# VF_sch.net
KiCad netlist of a schematic drawn in Altium Designer
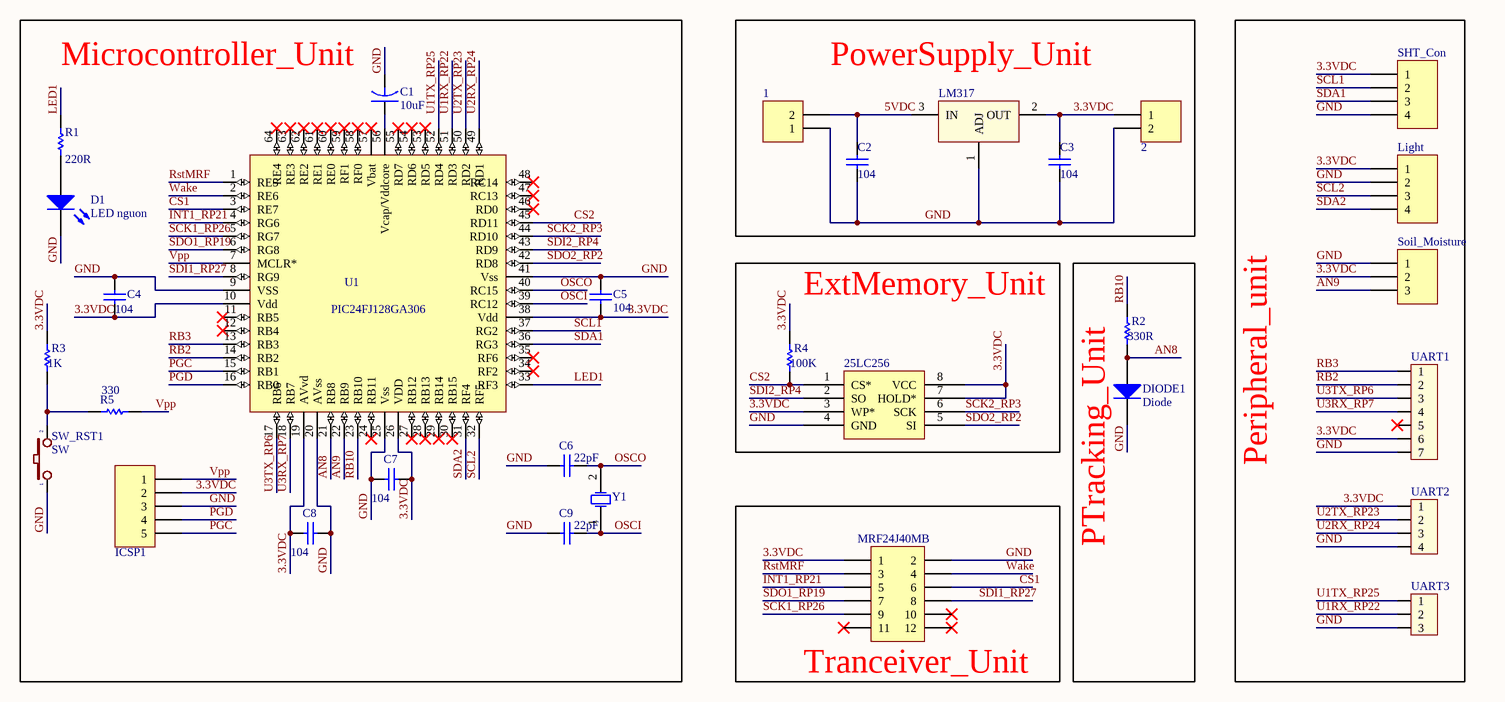
[diagram p0: VF_sch.SchDoc]

(export (version "E")
  (design (tool "Eeschema 10.0.6"))
  (components
    (comp (ref "1")
      (value "Header 2")
      (footprint "HDR1X2")
      (description "Header, 2-Pin")
      (fields (field (name "PUBLISHER") "Altium Limited"))
      (libsource (lib "") (part "Header 2_1"))
    )
    (comp (ref "2")
      (value "3.3V DC")
      (footprint "HDR1X2")
      (description "Header, 2-Pin")
      (fields (field (name "PUBLISHER") "Altium Limited"))
      (libsource (lib "Miscellaneous Connectors") (part "Header 2"))
    )
    (comp (ref "3") (value "25LC256") (footprint "DIP-8") (libsource (lib "25LC256") (part "25LC256")))
    (comp (ref "C1")
      (value "10uF")
      (footprint "MH_DA_THU_VIEN_16122016:CP1/2.5_SM")
      (libsource (lib "ThinhNguyenLib") (part "CAPACITOR"))
    )
    (comp (ref "C2")
      (value "104")
      (footprint "C0805")
      (description "Capacitor")
      (fields (field (name "Comment") "Cap") (field (name "PUBLISHER") "Altium Limited"))
      (libsource (lib "Miscellaneous Devices") (part "Cap"))
    )
    (comp (ref "C3")
      (value "104")
      (footprint "C0805")
      (description "Capacitor")
      (fields (field (name "Comment") "Cap") (field (name "PUBLISHER") "Altium Limited"))
      (libsource (lib "Miscellaneous Devices") (part "Cap"))
    )
    (comp (ref "C4")
      (value "104")
      (footprint "C0805")
      (description "Capacitor")
      (fields (field (name "Comment") "Cap") (field (name "PUBLISHER") "Altium Limited"))
      (libsource (lib "Miscellaneous Devices") (part "Cap"))
    )
    (comp (ref "C5")
      (value "104")
      (footprint "RAD-0.3")
      (description "Capacitor")
      (fields (field (name "PUBLISHER") "Altium Limited"))
      (libsource (lib "Miscellaneous Devices") (part "Cap"))
    )
    (comp (ref "C6")
      (value "22pF")
      (footprint "C0805")
      (description "Capacitor")
      (fields (field (name "Comment") "Cap") (field (name "PUBLISHER") "Altium Limited"))
      (libsource (lib "Miscellaneous Devices") (part "Cap"))
    )
    (comp (ref "C7")
      (value "104")
      (footprint "C0805")
      (description "Capacitor")
      (fields (field (name "Comment") "Cap") (field (name "PUBLISHER") "Altium Limited"))
      (libsource (lib "Miscellaneous Devices") (part "Cap"))
    )
    (comp (ref "C8")
      (value "104")
      (footprint "C0805")
      (description "Capacitor")
      (fields (field (name "Comment") "Cap") (field (name "PUBLISHER") "Altium Limited"))
      (libsource (lib "Miscellaneous Devices") (part "Cap"))
    )
    (comp (ref "C9")
      (value "22pF")
      (footprint "C0805")
      (description "Capacitor")
      (fields (field (name "Comment") "Cap") (field (name "PUBLISHER") "Altium Limited"))
      (libsource (lib "Miscellaneous Devices") (part "Cap"))
    )
    (comp (ref "D1")
      (value "LED nguon")
      (footprint "LED3mm")
      (description "Typical INFRARED GaAs LED")
      (fields (field (name "PUBLISHER") "Altium Limited"))
      (libsource (lib "Miscellaneous Devices") (part "LED0"))
    )
    (comp (ref "DIODE1")
      (value "Diode")
      (footprint "DZ0.5A")
      (description "Default Diode")
      (fields (field (name "PUBLISHER") "Altium Limited"))
      (libsource (lib "Miscellaneous Devices") (part "Diode"))
    )
    (comp (ref "ICSP1")
      (value "ICSP")
      (footprint "CON5")
      (description "Header, 5-Pin")
      (fields (field (name "PUBLISHER") "Altium Limited"))
      (libsource (lib "Miscellaneous Connectors") (part "Header 5"))
    )
    (comp (ref "LM317")
      (value "LM317")
      (footprint "SOT223-4N")
      (description "Adj Voltage +1.2 -> +37V")
      (libsource (lib "syhaunguyen") (part "LM317"))
    )
    (comp (ref "MRF1")
      (value "MRF24J40MB")
      (footprint "HDR2X6")
      (description "Header, 6-Pin, Dual row")
      (fields (field (name "PUBLISHER") "Altium Limited"))
      (libsource (lib "Miscellaneous Connectors") (part "Header 6X2"))
    )
    (comp (ref "P1")
      (value "Light")
      (footprint "HDR1X4")
      (description "Header, 4-Pin")
      (fields (field (name "PUBLISHER") "Altium Limited"))
      (libsource (lib "Miscellaneous Connectors") (part "Header 4"))
    )
    (comp (ref "R1")
      (value "220R")
      (footprint "C0805")
      (description "Resistor")
      (fields (field (name "Comment") "Res1") (field (name "PUBLISHER") "Altium Limited"))
      (libsource (lib "Miscellaneous Devices") (part "Res1"))
    )
    (comp (ref "R2")
      (value "330R")
      (footprint "C0805")
      (description "Resistor")
      (fields (field (name "Comment") "Res1") (field (name "PUBLISHER") "Altium Limited"))
      (libsource (lib "Miscellaneous Devices") (part "Res1"))
    )
    (comp (ref "R3")
      (value "1K")
      (footprint "C0805")
      (description "Resistor")
      (fields (field (name "Comment") "Res1") (field (name "PUBLISHER") "Altium Limited"))
      (libsource (lib "Miscellaneous Devices") (part "Res1"))
    )
    (comp (ref "R4")
      (value "100K")
      (footprint "C0805")
      (description "Semiconductor Resistor")
      (fields (field (name "Comment") "Res Semi") (field (name "PUBLISHER") "Altium Limited"))
      (libsource (lib "Miscellaneous Devices") (part "Res Semi"))
    )
    (comp (ref "R5")
      (value "330")
      (footprint "C0805")
      (description "Resistor")
      (fields (field (name "Comment") "res") (field (name "PUBLISHER") "Altium Limited"))
      (libsource (lib "Miscellaneous Devices") (part "Res1"))
    )
    (comp (ref "SHT_CON1")
      (value "SHT_Con")
      (footprint "CON4")
      (description "Header, 4-Pin")
      (fields (field (name "PUBLISHER") "Altium Limited"))
      (libsource (lib "Miscellaneous Connectors") (part "Header 4"))
    )
    (comp (ref "Soil_Moisture")
      (value "Header 3")
      (footprint "HDR1X3")
      (description "Header, 3-Pin")
      (fields (field (name "PUBLISHER") "Altium Limited"))
      (libsource (lib "Miscellaneous Connectors") (part "Header 3"))
    )
    (comp (ref "SW_RST1")
      (value "SW")
      (footprint "SW2")
      (description "Switch button 2 pin")
      (libsource (lib "syhaunguyen") (part "SW2"))
    )
    (comp (ref "U1")
      (value "PIC24FJ128GA306")
      (footprint "MCHP-TQFP-PT64_M")
      (libsource (lib "Mylibbrary") (part "PIC24FJ128GA306"))
    )
    (comp (ref "UART1")
      (value "LORA_TRANCEIVER")
      (footprint "CON7")
      (description "Connector 7")
      (libsource (lib "syhaunguyen") (part "Con7"))
    )
    (comp (ref "UART2")
      (value "UART2")
      (footprint "CON4")
      (description "Connector 4")
      (libsource (lib "syhaunguyen") (part "Con4"))
    )
    (comp (ref "UART3")
      (value "~")
      (footprint "CON3")
      (description "Connector 3")
      (libsource (lib "syhaunguyen") (part "Con3"))
    )
    (comp (ref "Y1")
      (value "XTAL")
      (footprint "XT2")
      (description "Crystal Oscillator")
      (fields (field (name "PUBLISHER") "Altium Limited"))
      (libsource (lib "Miscellaneous Devices") (part "XTAL"))
    )
  )
  (nets
    (net (code "1") (name "/3.3VDC") (class "Default")
      (node (ref "2") (pin "1") (pinfunction "1_1") (pintype "passive"))
      (node (ref "3") (pin "3") (pinfunction "WP*_3") (pintype "passive"))
      (node (ref "3") (pin "7") (pinfunction "HOLD*_7") (pintype "passive"))
      (node (ref "3") (pin "8") (pinfunction "VCC_8") (pintype "power_in"))
      (node (ref "C3") (pin "2") (pinfunction "2_2") (pintype "passive"))
      (node (ref "C4") (pin "1") (pinfunction "1_1") (pintype "passive"))
      (node (ref "C5") (pin "1") (pinfunction "1_1") (pintype "passive"))
      (node (ref "C7") (pin "2") (pinfunction "2_2") (pintype "passive"))
      (node (ref "C8") (pin "1") (pinfunction "1_1") (pintype "passive"))
      (node (ref "ICSP1") (pin "2") (pinfunction "2_2") (pintype "passive"))
      (node (ref "LM317") (pin "2") (pinfunction "OUT_2") (pintype "passive"))
      (node (ref "MRF1") (pin "1") (pinfunction "1_1") (pintype "passive"))
      (node (ref "P1") (pin "1") (pinfunction "1_1") (pintype "passive"))
      (node (ref "R3") (pin "2") (pinfunction "2_2") (pintype "passive"))
      (node (ref "R4") (pin "2") (pinfunction "2_2") (pintype "passive"))
      (node (ref "SHT_CON1") (pin "1") (pinfunction "1_1") (pintype "passive"))
      (node (ref "Soil_Moisture") (pin "2") (pinfunction "2_2") (pintype "passive"))
      (node (ref "U1") (pin "10") (pinfunction "Vdd_10") (pintype "passive"))
      (node (ref "U1") (pin "19") (pinfunction "AVvd_19") (pintype "power_in"))
      (node (ref "U1") (pin "26") (pinfunction "VDD_26") (pintype "power_in"))
      (node (ref "U1") (pin "38") (pinfunction "Vdd_38") (pintype "power_in"))
      (node (ref "UART1") (pin "6") (pinfunction "6_6") (pintype "passive"))
      (node (ref "UART2") (pin "1") (pinfunction "1_1") (pintype "passive"))
    )
    (net (code "2") (name "/5VDC") (class "Default")
      (node (ref "1") (pin "2") (pinfunction "2_2") (pintype "passive"))
      (node (ref "C2") (pin "2") (pinfunction "2_2") (pintype "passive"))
      (node (ref "LM317") (pin "3") (pinfunction "IN_3") (pintype "passive"))
    )
    (net (code "3") (name "/AN8") (class "Default")
      (node (ref "DIODE1") (pin "1") (pinfunction "A_1") (pintype "passive"))
      (node (ref "R2") (pin "1") (pinfunction "1_1") (pintype "passive"))
      (node (ref "U1") (pin "21") (pinfunction "RB8_21") (pintype "bidirectional"))
    )
    (net (code "4") (name "/AN9") (class "Default")
      (node (ref "Soil_Moisture") (pin "3") (pinfunction "3_3") (pintype "passive"))
      (node (ref "U1") (pin "22") (pinfunction "RB9_22") (pintype "bidirectional"))
    )
    (net (code "5") (name "/CS1") (class "Default")
      (node (ref "MRF1") (pin "6") (pinfunction "6_6") (pintype "passive"))
      (node (ref "U1") (pin "3") (pinfunction "RE7_3") (pintype "bidirectional"))
    )
    (net (code "6") (name "/CS2") (class "Default")
      (node (ref "3") (pin "1") (pinfunction "CS*_1") (pintype "passive"))
      (node (ref "R4") (pin "1") (pinfunction "1_1") (pintype "passive"))
      (node (ref "U1") (pin "45") (pinfunction "RD11_45") (pintype "bidirectional"))
    )
    (net (code "7") (name "/GND") (class "Default")
      (node (ref "1") (pin "1") (pinfunction "1_1") (pintype "passive"))
      (node (ref "2") (pin "2") (pinfunction "2_2") (pintype "passive"))
      (node (ref "3") (pin "4") (pinfunction "GND_4") (pintype "power_in"))
      (node (ref "C1") (pin "2") (pinfunction "2_2") (pintype "passive"))
      (node (ref "C2") (pin "1") (pinfunction "1_1") (pintype "passive"))
      (node (ref "C3") (pin "1") (pinfunction "1_1") (pintype "passive"))
      (node (ref "C4") (pin "2") (pinfunction "2_2") (pintype "passive"))
      (node (ref "C5") (pin "2") (pinfunction "2_2") (pintype "passive"))
      (node (ref "C6") (pin "1") (pinfunction "1_1") (pintype "passive"))
      (node (ref "C7") (pin "1") (pinfunction "1_1") (pintype "passive"))
      (node (ref "C8") (pin "2") (pinfunction "2_2") (pintype "passive"))
      (node (ref "C9") (pin "1") (pinfunction "1_1") (pintype "passive"))
      (node (ref "D1") (pin "2") (pinfunction "K_2") (pintype "passive"))
      (node (ref "DIODE1") (pin "2") (pinfunction "K_2") (pintype "passive"))
      (node (ref "ICSP1") (pin "3") (pinfunction "3_3") (pintype "passive"))
      (node (ref "LM317") (pin "1") (pinfunction "ADJ_1") (pintype "passive"))
      (node (ref "MRF1") (pin "2") (pinfunction "2_2") (pintype "passive"))
      (node (ref "P1") (pin "2") (pinfunction "2_2") (pintype "passive"))
      (node (ref "SHT_CON1") (pin "4") (pinfunction "4_4") (pintype "passive"))
      (node (ref "SW_RST1") (pin "1") (pinfunction "1_1") (pintype "passive"))
      (node (ref "Soil_Moisture") (pin "1") (pinfunction "1_1") (pintype "passive"))
      (node (ref "U1") (pin "20") (pinfunction "AVss_20") (pintype "power_in"))
      (node (ref "U1") (pin "25") (pinfunction "Vss_25") (pintype "power_in"))
      (node (ref "U1") (pin "41") (pinfunction "Vss_41") (pintype "power_in"))
      (node (ref "U1") (pin "9") (pinfunction "VSS_9") (pintype "power_in"))
      (node (ref "UART1") (pin "7") (pinfunction "7_7") (pintype "passive"))
      (node (ref "UART2") (pin "4") (pinfunction "4_4") (pintype "passive"))
      (node (ref "UART3") (pin "3") (pinfunction "3_3") (pintype "passive"))
    )
    (net (code "8") (name "/INT1_RP21") (class "Default")
      (node (ref "MRF1") (pin "5") (pinfunction "5_5") (pintype "passive"))
      (node (ref "U1") (pin "4") (pinfunction "RG6_4") (pintype "bidirectional"))
    )
    (net (code "9") (name "/LED1") (class "Default")
      (node (ref "R1") (pin "2") (pinfunction "2_2") (pintype "passive"))
      (node (ref "U1") (pin "33") (pinfunction "RF3_33") (pintype "bidirectional"))
    )
    (net (code "10") (name "/OSCI") (class "Default")
      (node (ref "C9") (pin "2") (pinfunction "2_2") (pintype "passive"))
      (node (ref "U1") (pin "39") (pinfunction "RC12_39") (pintype "bidirectional"))
      (node (ref "Y1") (pin "1") (pinfunction "OSC1_1") (pintype "passive"))
    )
    (net (code "11") (name "/OSCO") (class "Default")
      (node (ref "C6") (pin "2") (pinfunction "2_2") (pintype "passive"))
      (node (ref "U1") (pin "40") (pinfunction "RC15_40") (pintype "bidirectional"))
      (node (ref "Y1") (pin "2") (pinfunction "OSC2_2") (pintype "passive"))
    )
    (net (code "12") (name "/PGC") (class "Default")
      (node (ref "ICSP1") (pin "5") (pinfunction "5_5") (pintype "passive"))
      (node (ref "U1") (pin "15") (pinfunction "RB1_15") (pintype "bidirectional"))
    )
    (net (code "13") (name "/PGD") (class "Default")
      (node (ref "ICSP1") (pin "4") (pinfunction "4_4") (pintype "passive"))
      (node (ref "U1") (pin "16") (pinfunction "RB0_16") (pintype "bidirectional"))
    )
    (net (code "14") (name "/RB2") (class "Default")
      (node (ref "U1") (pin "14") (pinfunction "RB2_14") (pintype "bidirectional"))
      (node (ref "UART1") (pin "2") (pinfunction "2_2") (pintype "passive"))
    )
    (net (code "15") (name "/RB3") (class "Default")
      (node (ref "U1") (pin "13") (pinfunction "RB3_13") (pintype "bidirectional"))
      (node (ref "UART1") (pin "1") (pinfunction "1_1") (pintype "passive"))
    )
    (net (code "16") (name "/RB10") (class "Default")
      (node (ref "R2") (pin "2") (pinfunction "2_2") (pintype "passive"))
      (node (ref "U1") (pin "23") (pinfunction "RB10_23") (pintype "bidirectional"))
    )
    (net (code "17") (name "/RstMRF") (class "Default")
      (node (ref "MRF1") (pin "3") (pinfunction "3_3") (pintype "passive"))
      (node (ref "U1") (pin "1") (pinfunction "RE5_1") (pintype "bidirectional"))
    )
    (net (code "18") (name "/SCK1_RP26") (class "Default")
      (node (ref "MRF1") (pin "9") (pinfunction "9_9") (pintype "passive"))
      (node (ref "U1") (pin "5") (pinfunction "RG7_5") (pintype "bidirectional"))
    )
    (net (code "19") (name "/SCK2_RP3") (class "Default")
      (node (ref "3") (pin "6") (pinfunction "SCK_6") (pintype "passive"))
      (node (ref "U1") (pin "44") (pinfunction "RD10_44") (pintype "bidirectional"))
    )
    (net (code "20") (name "/SCL1") (class "Default")
      (node (ref "SHT_CON1") (pin "2") (pinfunction "2_2") (pintype "passive"))
      (node (ref "U1") (pin "37") (pinfunction "RG2_37") (pintype "bidirectional"))
    )
    (net (code "21") (name "/SCL2") (class "Default")
      (node (ref "P1") (pin "3") (pinfunction "3_3") (pintype "passive"))
      (node (ref "U1") (pin "32") (pinfunction "RF5_32") (pintype "bidirectional"))
    )
    (net (code "22") (name "/SDA1") (class "Default")
      (node (ref "SHT_CON1") (pin "3") (pinfunction "3_3") (pintype "passive"))
      (node (ref "U1") (pin "36") (pinfunction "RG3_36") (pintype "bidirectional"))
    )
    (net (code "23") (name "/SDA2") (class "Default")
      (node (ref "P1") (pin "4") (pinfunction "4_4") (pintype "passive"))
      (node (ref "U1") (pin "31") (pinfunction "RF4_31") (pintype "bidirectional"))
    )
    (net (code "24") (name "/SDI1_RP27") (class "Default")
      (node (ref "MRF1") (pin "8") (pinfunction "8_8") (pintype "passive"))
      (node (ref "U1") (pin "8") (pinfunction "RG9_8") (pintype "bidirectional"))
    )
    (net (code "25") (name "/SDI2_RP4") (class "Default")
      (node (ref "3") (pin "2") (pinfunction "SO_2") (pintype "passive"))
      (node (ref "U1") (pin "43") (pinfunction "RD9_43") (pintype "bidirectional"))
    )
    (net (code "26") (name "/SDO1_RP19") (class "Default")
      (node (ref "MRF1") (pin "7") (pinfunction "7_7") (pintype "passive"))
      (node (ref "U1") (pin "6") (pinfunction "RG8_6") (pintype "bidirectional"))
    )
    (net (code "27") (name "/SDO2_RP2") (class "Default")
      (node (ref "3") (pin "5") (pinfunction "SI_5") (pintype "passive"))
      (node (ref "U1") (pin "42") (pinfunction "RD8_42") (pintype "bidirectional"))
    )
    (net (code "28") (name "/U1RX_RP22") (class "Default")
      (node (ref "U1") (pin "51") (pinfunction "RD3_51") (pintype "bidirectional"))
      (node (ref "UART3") (pin "2") (pinfunction "2_2") (pintype "passive"))
    )
    (net (code "29") (name "/U1TX_RP25") (class "Default")
      (node (ref "U1") (pin "52") (pinfunction "RD4_52") (pintype "bidirectional"))
      (node (ref "UART3") (pin "1") (pinfunction "1_1") (pintype "passive"))
    )
    (net (code "30") (name "/U2RX_RP24") (class "Default")
      (node (ref "U1") (pin "49") (pinfunction "RD1_49") (pintype "bidirectional"))
      (node (ref "UART2") (pin "3") (pinfunction "3_3") (pintype "passive"))
    )
    (net (code "31") (name "/U2TX_RP23") (class "Default")
      (node (ref "U1") (pin "50") (pinfunction "RD2_50") (pintype "bidirectional"))
      (node (ref "UART2") (pin "2") (pinfunction "2_2") (pintype "passive"))
    )
    (net (code "32") (name "/U3RX_RP7") (class "Default")
      (node (ref "U1") (pin "18") (pinfunction "RB7_18") (pintype "bidirectional"))
      (node (ref "UART1") (pin "4") (pinfunction "4_4") (pintype "passive"))
    )
    (net (code "33") (name "/U3TX_RP6") (class "Default")
      (node (ref "U1") (pin "17") (pinfunction "RB6_17") (pintype "bidirectional"))
      (node (ref "UART1") (pin "3") (pinfunction "3_3") (pintype "passive"))
    )
    (net (code "34") (name "/Vpp") (class "Default")
      (node (ref "ICSP1") (pin "1") (pinfunction "1_1") (pintype "passive"))
      (node (ref "R5") (pin "2") (pinfunction "2_2") (pintype "passive"))
      (node (ref "U1") (pin "7") (pinfunction "MCLR*_7") (pintype "passive"))
    )
    (net (code "35") (name "/Wake") (class "Default")
      (node (ref "MRF1") (pin "4") (pinfunction "4_4") (pintype "passive"))
      (node (ref "U1") (pin "2") (pinfunction "RE6_2") (pintype "bidirectional"))
    )
    (net (code "36") (name "Net-(D1-A)") (class "Default")
      (node (ref "D1") (pin "1") (pinfunction "A_1") (pintype "passive"))
      (node (ref "R1") (pin "1") (pinfunction "1_1") (pintype "passive"))
    )
    (net (code "37") (name "Net-(R3-Pad1)") (class "Default")
      (node (ref "R3") (pin "1") (pinfunction "1_1") (pintype "passive"))
      (node (ref "R5") (pin "1") (pinfunction "1_1") (pintype "passive"))
      (node (ref "SW_RST1") (pin "2") (pinfunction "2_2") (pintype "passive"))
    )
    (net (code "38") (name "Net-(U1-Vcap{slash}Vddcore)") (class "Default")
      (node (ref "C1") (pin "1") (pinfunction "1_1") (pintype "passive"))
      (node (ref "U1") (pin "56") (pinfunction "Vcap/Vddcore_56") (pintype "power_in"))
    )
    (net (code "39") (name "unconnected-(MRF1-Pad10)") (class "Default")
      (node (ref "MRF1") (pin "10") (pinfunction "10_10") (pintype "passive+no_connect"))
    )
    (net (code "40") (name "unconnected-(MRF1-Pad11)") (class "Default")
      (node (ref "MRF1") (pin "11") (pinfunction "11_11") (pintype "passive+no_connect"))
    )
    (net (code "41") (name "unconnected-(MRF1-Pad12)") (class "Default")
      (node (ref "MRF1") (pin "12") (pinfunction "12_12") (pintype "passive+no_connect"))
    )
    (net (code "42") (name "unconnected-(U1-RB4-Pad12)") (class "Default")
      (node (ref "U1") (pin "12") (pinfunction "RB4_12") (pintype "bidirectional+no_connect"))
    )
    (net (code "43") (name "unconnected-(U1-RB5-Pad11)") (class "Default")
      (node (ref "U1") (pin "11") (pinfunction "RB5_11") (pintype "bidirectional+no_connect"))
    )
    (net (code "44") (name "unconnected-(U1-RB11-Pad24)") (class "Default")
      (node (ref "U1") (pin "24") (pinfunction "RB11_24") (pintype "bidirectional+no_connect"))
    )
    (net (code "45") (name "unconnected-(U1-RB12-Pad27)") (class "Default")
      (node (ref "U1") (pin "27") (pinfunction "RB12_27") (pintype "bidirectional+no_connect"))
    )
    (net (code "46") (name "unconnected-(U1-RB13-Pad28)") (class "Default")
      (node (ref "U1") (pin "28") (pinfunction "RB13_28") (pintype "bidirectional+no_connect"))
    )
    (net (code "47") (name "unconnected-(U1-RB14-Pad29)") (class "Default")
      (node (ref "U1") (pin "29") (pinfunction "RB14_29") (pintype "bidirectional+no_connect"))
    )
    (net (code "48") (name "unconnected-(U1-RB15-Pad30)") (class "Default")
      (node (ref "U1") (pin "30") (pinfunction "RB15_30") (pintype "bidirectional+no_connect"))
    )
    (net (code "49") (name "unconnected-(U1-RC13-Pad47)") (class "Default")
      (node (ref "U1") (pin "47") (pinfunction "RC13_47") (pintype "bidirectional+no_connect"))
    )
    (net (code "50") (name "unconnected-(U1-RC14-Pad48)") (class "Default")
      (node (ref "U1") (pin "48") (pinfunction "RC14_48") (pintype "bidirectional+no_connect"))
    )
    (net (code "51") (name "unconnected-(U1-RD0-Pad46)") (class "Default")
      (node (ref "U1") (pin "46") (pinfunction "RD0_46") (pintype "bidirectional+no_connect"))
    )
    (net (code "52") (name "unconnected-(U1-RD5-Pad53)") (class "Default")
      (node (ref "U1") (pin "53") (pinfunction "RD5_53") (pintype "bidirectional+no_connect"))
    )
    (net (code "53") (name "unconnected-(U1-RD6-Pad54)") (class "Default")
      (node (ref "U1") (pin "54") (pinfunction "RD6_54") (pintype "bidirectional+no_connect"))
    )
    (net (code "54") (name "unconnected-(U1-RD7-Pad55)") (class "Default")
      (node (ref "U1") (pin "55") (pinfunction "RD7_55") (pintype "bidirectional+no_connect"))
    )
    (net (code "55") (name "unconnected-(U1-RE0-Pad60)") (class "Default")
      (node (ref "U1") (pin "60") (pinfunction "RE0_60") (pintype "bidirectional+no_connect"))
    )
    (net (code "56") (name "unconnected-(U1-RE1-Pad61)") (class "Default")
      (node (ref "U1") (pin "61") (pinfunction "RE1_61") (pintype "bidirectional+no_connect"))
    )
    (net (code "57") (name "unconnected-(U1-RE2-Pad62)") (class "Default")
      (node (ref "U1") (pin "62") (pinfunction "RE2_62") (pintype "bidirectional+no_connect"))
    )
    (net (code "58") (name "unconnected-(U1-RE3-Pad63)") (class "Default")
      (node (ref "U1") (pin "63") (pinfunction "RE3_63") (pintype "bidirectional+no_connect"))
    )
    (net (code "59") (name "unconnected-(U1-RE4-Pad64)") (class "Default")
      (node (ref "U1") (pin "64") (pinfunction "RE4_64") (pintype "bidirectional+no_connect"))
    )
    (net (code "60") (name "unconnected-(U1-RF0-Pad58)") (class "Default")
      (node (ref "U1") (pin "58") (pinfunction "RF0_58") (pintype "bidirectional+no_connect"))
    )
    (net (code "61") (name "unconnected-(U1-RF1-Pad59)") (class "Default")
      (node (ref "U1") (pin "59") (pinfunction "RF1_59") (pintype "bidirectional+no_connect"))
    )
    (net (code "62") (name "unconnected-(U1-RF2-Pad34)") (class "Default")
      (node (ref "U1") (pin "34") (pinfunction "RF2_34") (pintype "bidirectional+no_connect"))
    )
    (net (code "63") (name "unconnected-(U1-RF6-Pad35)") (class "Default")
      (node (ref "U1") (pin "35") (pinfunction "RF6_35") (pintype "bidirectional+no_connect"))
    )
    (net (code "64") (name "unconnected-(U1-Vbat-Pad57)") (class "Default")
      (node (ref "U1") (pin "57") (pinfunction "Vbat_57") (pintype "power_in+no_connect"))
    )
    (net (code "65") (name "unconnected-(UART1-Pad5)") (class "Default")
      (node (ref "UART1") (pin "5") (pinfunction "5_5") (pintype "passive+no_connect"))
    )
  )
)
